# Sheet1.net
KiCad netlist of a schematic drawn in Altium Designer
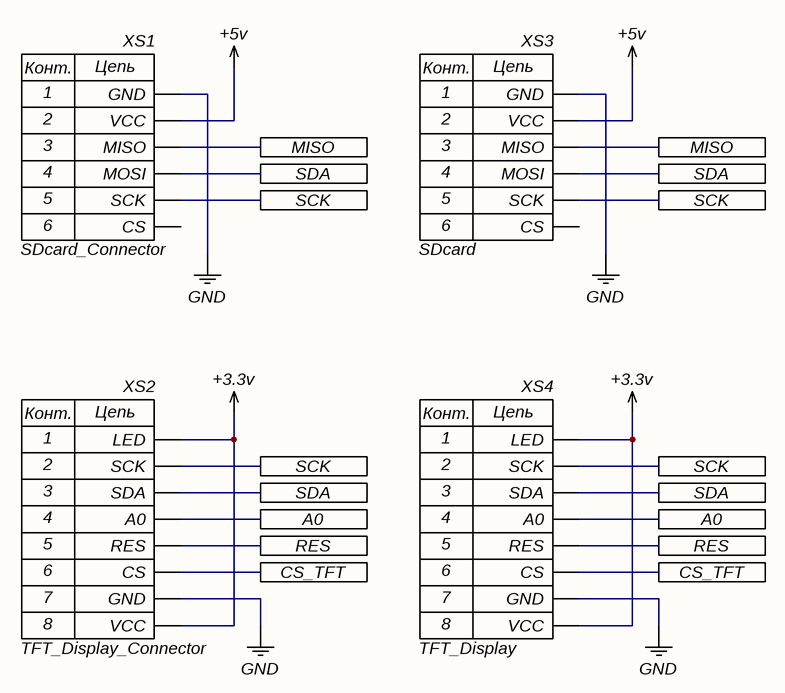
[diagram p0: Sheet1.SchDoc]

(export (version "E")
  (design (tool "Eeschema 10.0.6"))
  (components
    (comp (ref "XS1")
      (value "SDcard_Connector")
      (footprint "PinOutX6")
      (libsource (lib "Schlib1") (part "SDcard_Connector"))
    )
    (comp (ref "XS2")
      (value "TFT_Display_Connector")
      (footprint "PinOutX8")
      (libsource (lib "Schlib1") (part "TFT_Display_Connector"))
    )
    (comp (ref "XS3") (value "SDcard") (footprint "SDcard") (libsource (lib "Schlib1") (part "SDcard")))
    (comp (ref "XS4")
      (value "TFT_Display")
      (footprint "TFT")
      (libsource (lib "Schlib1") (part "TFT_Display"))
    )
  )
  (nets
    (net (code "1") (name "+3.3v") (class "Default")
      (node (ref "XS2") (pin "1") (pinfunction "LED_1") (pintype "passive"))
      (node (ref "XS2") (pin "8") (pinfunction "VCC_8") (pintype "passive"))
      (node (ref "XS4") (pin "1") (pinfunction "LED_1") (pintype "passive"))
      (node (ref "XS4") (pin "8") (pinfunction "VCC_8") (pintype "passive"))
    )
    (net (code "2") (name "+5v") (class "Default")
      (node (ref "XS1") (pin "2") (pinfunction "VCC_2") (pintype "passive"))
      (node (ref "XS3") (pin "2") (pinfunction "VCC_2") (pintype "passive"))
    )
    (net (code "3") (name "/A0") (class "Default")
      (node (ref "XS2") (pin "4") (pinfunction "A0_4") (pintype "passive"))
      (node (ref "XS4") (pin "4") (pinfunction "A0_4") (pintype "passive"))
    )
    (net (code "4") (name "/CS_TFT") (class "Default")
      (node (ref "XS2") (pin "6") (pinfunction "CS_6") (pintype "passive"))
      (node (ref "XS4") (pin "6") (pinfunction "CS_6") (pintype "passive"))
    )
    (net (code "5") (name "/MISO") (class "Default")
      (node (ref "XS1") (pin "3") (pinfunction "MISO_3") (pintype "passive"))
      (node (ref "XS3") (pin "3") (pinfunction "MISO_3") (pintype "passive"))
    )
    (net (code "6") (name "/RES") (class "Default")
      (node (ref "XS2") (pin "5") (pinfunction "RES_5") (pintype "passive"))
      (node (ref "XS4") (pin "5") (pinfunction "RES_5") (pintype "passive"))
    )
    (net (code "7") (name "/SCK") (class "Default")
      (node (ref "XS1") (pin "5") (pinfunction "SCK_5") (pintype "passive"))
      (node (ref "XS2") (pin "2") (pinfunction "SCK_2") (pintype "passive"))
      (node (ref "XS3") (pin "5") (pinfunction "SCK_5") (pintype "passive"))
      (node (ref "XS4") (pin "2") (pinfunction "SCK_2") (pintype "passive"))
    )
    (net (code "8") (name "/SDA") (class "Default")
      (node (ref "XS1") (pin "4") (pinfunction "MOSI_4") (pintype "passive"))
      (node (ref "XS2") (pin "3") (pinfunction "SDA_3") (pintype "passive"))
      (node (ref "XS3") (pin "4") (pinfunction "MOSI_4") (pintype "passive"))
      (node (ref "XS4") (pin "3") (pinfunction "SDA_3") (pintype "passive"))
    )
    (net (code "9") (name "GND") (class "Default")
      (node (ref "XS1") (pin "1") (pinfunction "GND_1") (pintype "passive"))
      (node (ref "XS2") (pin "7") (pinfunction "GND_7") (pintype "passive"))
      (node (ref "XS3") (pin "1") (pinfunction "GND_1") (pintype "passive"))
      (node (ref "XS4") (pin "7") (pinfunction "GND_7") (pintype "passive"))
    )
    (net (code "10") (name "unconnected-(XS1-CS-Pad6)") (class "Default")
      (node (ref "XS1") (pin "6") (pinfunction "CS_6") (pintype "passive"))
    )
    (net (code "11") (name "unconnected-(XS3-CS-Pad6)") (class "Default")
      (node (ref "XS3") (pin "6") (pinfunction "CS_6") (pintype "passive"))
    )
  )
)
